# qe.net
KiCad netlist of a schematic drawn in EAGLE
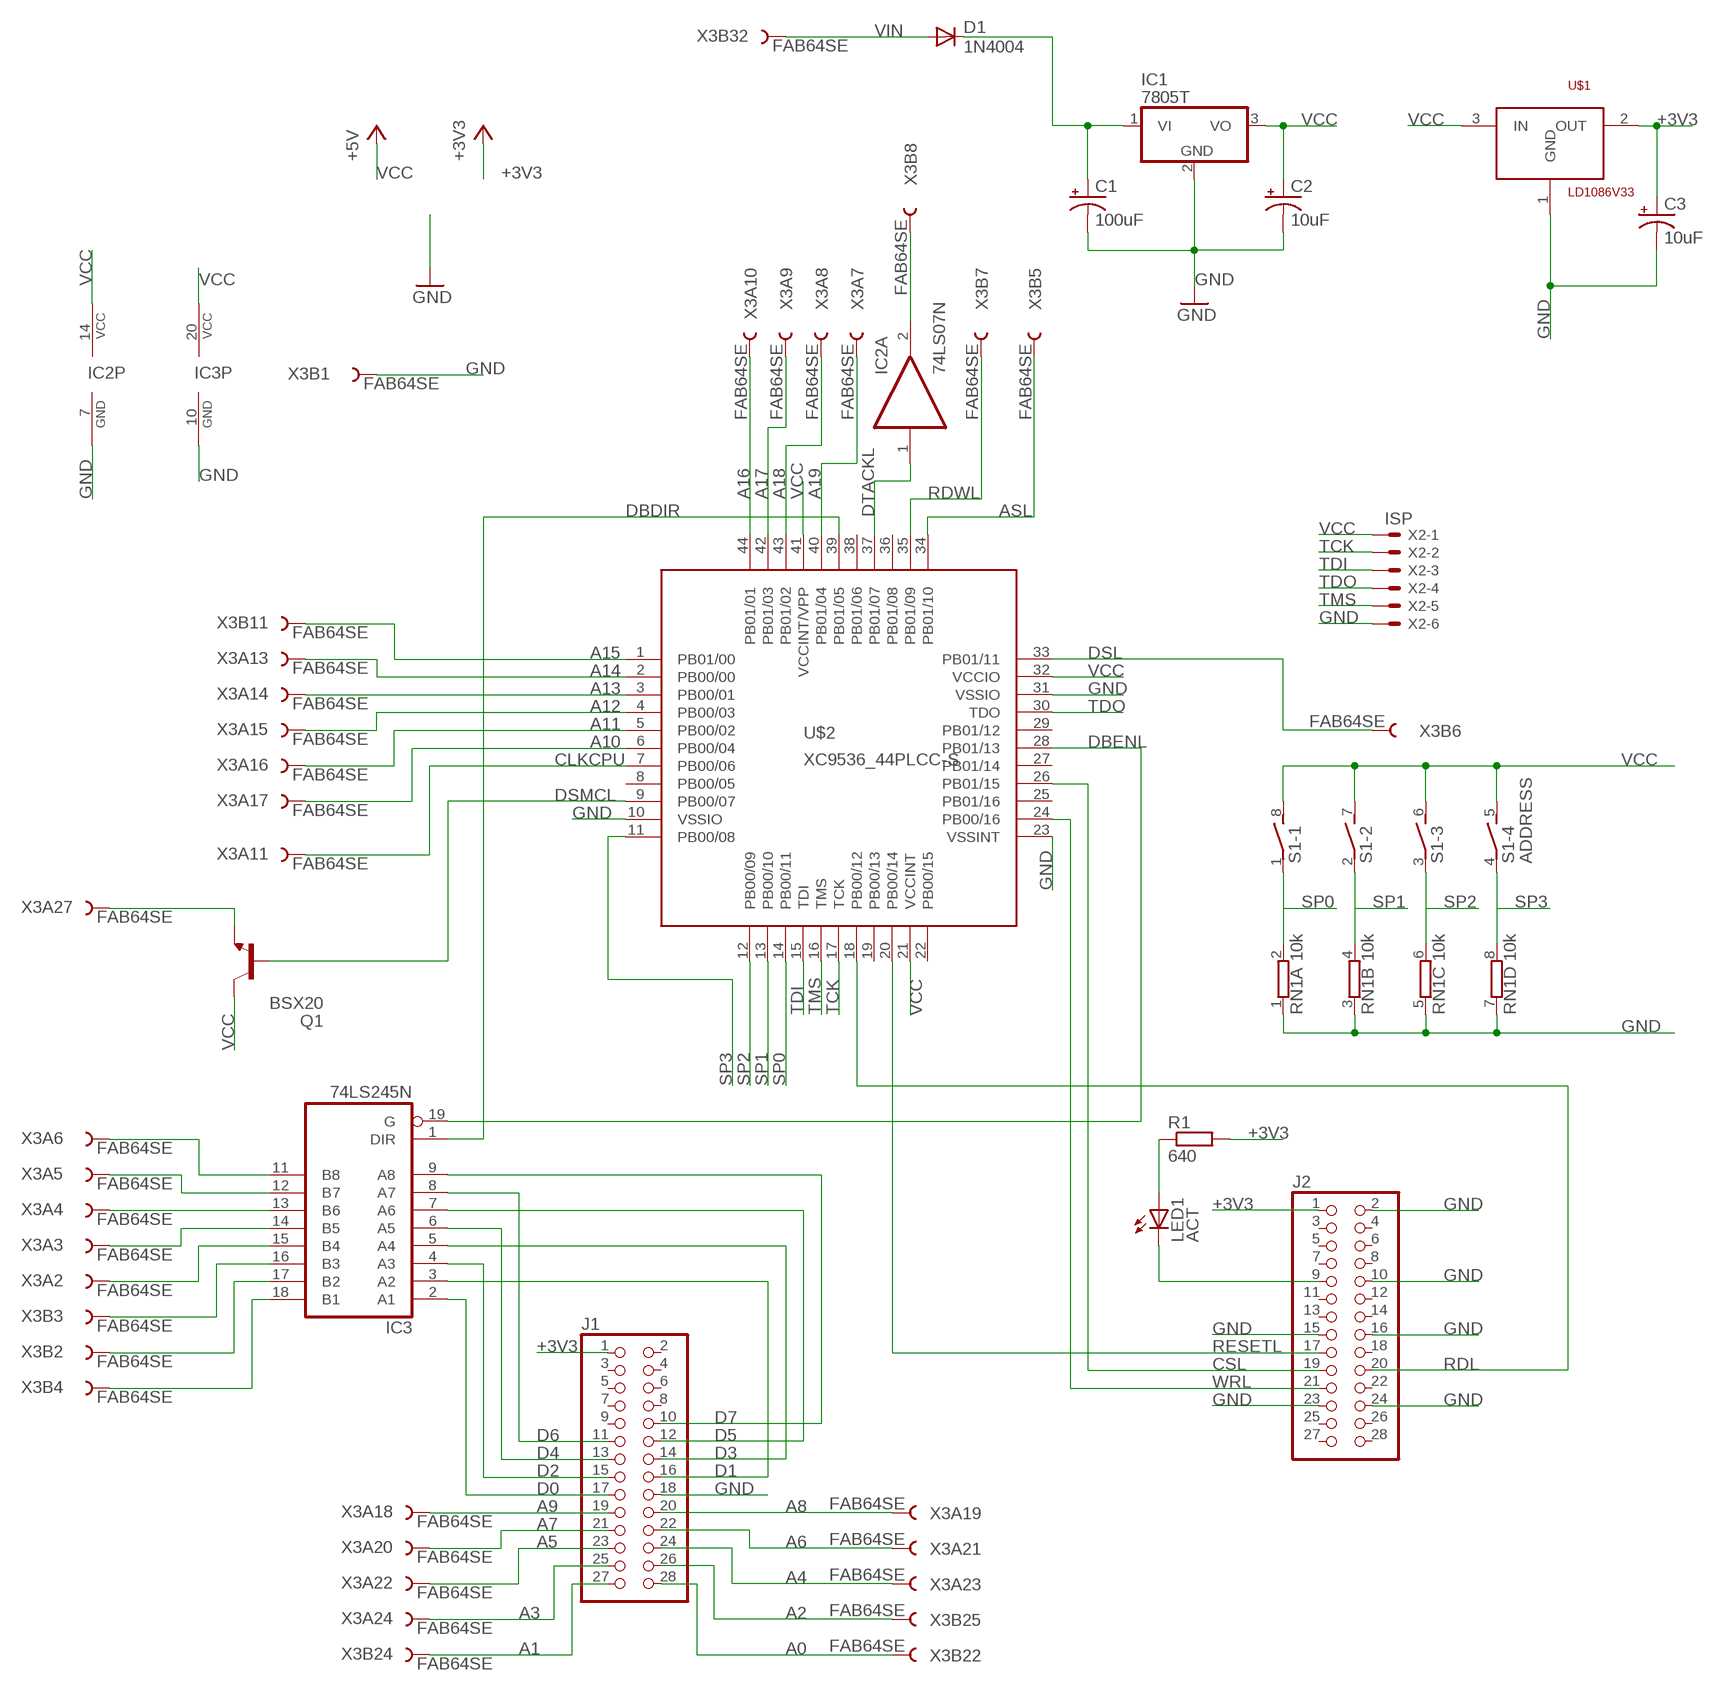
[diagram p0: schematic, sheet 1]

(export (version "E")
  (design (tool "Eeschema 10.0.6"))
  (components
    (comp (ref "C1")
      (value "100uF")
      (footprint "eagle-import:TAP5-80")
      (libsource (lib "eagle-import") (part "CPOL-USTAP5-80"))
    )
    (comp (ref "C2")
      (value "10uF")
      (footprint "eagle-import:TAP5-45")
      (libsource (lib "eagle-import") (part "CPOL-USTAP5-45"))
    )
    (comp (ref "C3")
      (value "10uF")
      (footprint "eagle-import:TAP5-45")
      (libsource (lib "eagle-import") (part "CPOL-USTAP5-45"))
    )
    (comp (ref "D1")
      (value "1N4004")
      (footprint "eagle-import:DO41-10")
      (libsource (lib "eagle-import") (part "1N4004"))
    )
    (comp (ref "IC1")
      (value "7805T")
      (footprint "eagle-import:TO220H")
      (libsource (lib "eagle-import") (part "78T05"))
    )
    (comp (ref "IC2")
      (value "74LS07N")
      (footprint "eagle-import:DIL14")
      (libsource (lib "eagle-import") (part "7407NLS"))
    )
    (comp (ref "IC3")
      (value "74LS245N")
      (footprint "eagle-import:DIL20")
      (libsource (lib "eagle-import") (part "74245NLS"))
    )
    (comp (ref "J1")
      (value "PINHD-2X14")
      (footprint "eagle-import:2X14")
      (libsource (lib "eagle-import") (part "PINHD-2X14"))
    )
    (comp (ref "J2")
      (value "PINHD-2X14")
      (footprint "eagle-import:2X14")
      (libsource (lib "eagle-import") (part "PINHD-2X14"))
    )
    (comp (ref "LED1")
      (value "ACT")
      (footprint "eagle-import:LED5MM")
      (libsource (lib "eagle-import") (part "LED5MM"))
    )
    (comp (ref "Q1")
      (value "BSX20")
      (footprint "eagle-import:TO18")
      (libsource (lib "eagle-import") (part "BSX20"))
    )
    (comp (ref "R1")
      (value "640")
      (footprint "eagle-import:0204_7")
      (libsource (lib "eagle-import") (part "R-EU_0204/7"))
    )
    (comp (ref "RN1")
      (value "10k")
      (footprint "eagle-import:SIL8")
      (libsource (lib "eagle-import") (part "E4R"))
    )
    (comp (ref "S1")
      (value "ADDRESS")
      (footprint "eagle-import:DIP04S")
      (libsource (lib "eagle-import") (part "DIP04S"))
    )
    (comp (ref "U$1")
      (value "LD1086V33")
      (footprint "eagle-import:TO220")
      (libsource (lib "eagle-import") (part "LD1086V33"))
    )
    (comp (ref "U$2")
      (value "XC9536_44PLCC-S")
      (footprint "eagle-import:PLCC44-S")
      (libsource (lib "eagle-import") (part "XC9536_44PLCC-S"))
    )
    (comp (ref "X2")
      (value "ISP")
      (footprint "eagle-import:22-23-2061")
      (libsource (lib "eagle-import") (part "22-23-2061"))
    )
    (comp (ref "X3")
      (value "FAB64SE")
      (footprint "eagle-import:FAB64S")
      (libsource (lib "eagle-import") (part "FAB64SE"))
    )
  )
  (nets
    (net (code "1") (name "+3V3") (class "Default")
      (node (ref "C3") (pin "+") (pinfunction "+_+") (pintype "passive"))
      (node (ref "J1") (pin "1") (pinfunction "1_1") (pintype "passive"))
      (node (ref "J2") (pin "1") (pinfunction "1_1") (pintype "passive"))
      (node (ref "R1") (pin "2") (pinfunction "2_2") (pintype "passive"))
      (node (ref "U$1") (pin "2") (pinfunction "OUT_2") (pintype "bidirectional"))
    )
    (net (code "2") (name "+5V") (class "Default")
      (node (ref "C2") (pin "+") (pinfunction "+_+") (pintype "passive"))
      (node (ref "IC1") (pin "3") (pinfunction "VO_3") (pintype "passive"))
      (node (ref "IC2") (pin "14") (pinfunction "VCC_14") (pintype "power_in"))
      (node (ref "IC3") (pin "20") (pinfunction "VCC_20") (pintype "power_in"))
      (node (ref "Q1") (pin "3") (pinfunction "C_3") (pintype "passive"))
      (node (ref "S1") (pin "5") (pinfunction "2_5") (pintype "passive"))
      (node (ref "S1") (pin "6") (pinfunction "2_6") (pintype "passive"))
      (node (ref "S1") (pin "7") (pinfunction "2_7") (pintype "passive"))
      (node (ref "S1") (pin "8") (pinfunction "2_8") (pintype "passive"))
      (node (ref "U$1") (pin "3") (pinfunction "IN_3") (pintype "bidirectional"))
      (node (ref "U$2") (pin "21") (pinfunction "VCCINT_21") (pintype "power_in"))
      (node (ref "U$2") (pin "32") (pinfunction "VCCIO_32") (pintype "power_in"))
      (node (ref "U$2") (pin "41") (pinfunction "VCCINT/VPP_41") (pintype "input"))
      (node (ref "X2") (pin "1") (pinfunction "S_1") (pintype "passive"))
    )
    (net (code "3") (name "/A0") (class "Default")
      (node (ref "J1") (pin "28") (pinfunction "28_28") (pintype "passive"))
      (node (ref "X3") (pin "B22") (pinfunction "B_B22") (pintype "passive"))
    )
    (net (code "4") (name "/A1") (class "Default")
      (node (ref "J1") (pin "27") (pinfunction "27_27") (pintype "passive"))
      (node (ref "X3") (pin "B24") (pinfunction "B_B24") (pintype "passive"))
    )
    (net (code "5") (name "/A2") (class "Default")
      (node (ref "J1") (pin "26") (pinfunction "26_26") (pintype "passive"))
      (node (ref "X3") (pin "B25") (pinfunction "B_B25") (pintype "passive"))
    )
    (net (code "6") (name "/A3") (class "Default")
      (node (ref "J1") (pin "25") (pinfunction "25_25") (pintype "passive"))
      (node (ref "X3") (pin "A24") (pinfunction "B_A24") (pintype "passive"))
    )
    (net (code "7") (name "/A4") (class "Default")
      (node (ref "J1") (pin "24") (pinfunction "24_24") (pintype "passive"))
      (node (ref "X3") (pin "A23") (pinfunction "B_A23") (pintype "passive"))
    )
    (net (code "8") (name "/A5") (class "Default")
      (node (ref "J1") (pin "23") (pinfunction "23_23") (pintype "passive"))
      (node (ref "X3") (pin "A22") (pinfunction "B_A22") (pintype "passive"))
    )
    (net (code "9") (name "/A6") (class "Default")
      (node (ref "J1") (pin "22") (pinfunction "22_22") (pintype "passive"))
      (node (ref "X3") (pin "A21") (pinfunction "B_A21") (pintype "passive"))
    )
    (net (code "10") (name "/A7") (class "Default")
      (node (ref "J1") (pin "21") (pinfunction "21_21") (pintype "passive"))
      (node (ref "X3") (pin "A20") (pinfunction "B_A20") (pintype "passive"))
    )
    (net (code "11") (name "/A8") (class "Default")
      (node (ref "J1") (pin "20") (pinfunction "20_20") (pintype "passive"))
      (node (ref "X3") (pin "A19") (pinfunction "B_A19") (pintype "passive"))
    )
    (net (code "12") (name "/A9") (class "Default")
      (node (ref "J1") (pin "19") (pinfunction "19_19") (pintype "passive"))
      (node (ref "X3") (pin "A18") (pinfunction "B_A18") (pintype "passive"))
    )
    (net (code "13") (name "/A10") (class "Default")
      (node (ref "U$2") (pin "6") (pinfunction "PB00/04_6") (pintype "bidirectional"))
      (node (ref "X3") (pin "A17") (pinfunction "B_A17") (pintype "passive"))
    )
    (net (code "14") (name "/A11") (class "Default")
      (node (ref "U$2") (pin "5") (pinfunction "PB00/02_5") (pintype "bidirectional"))
      (node (ref "X3") (pin "A16") (pinfunction "B_A16") (pintype "passive"))
    )
    (net (code "15") (name "/A12") (class "Default")
      (node (ref "U$2") (pin "4") (pinfunction "PB00/03_4") (pintype "bidirectional"))
      (node (ref "X3") (pin "A15") (pinfunction "B_A15") (pintype "passive"))
    )
    (net (code "16") (name "/A13") (class "Default")
      (node (ref "U$2") (pin "3") (pinfunction "PB00/01_3") (pintype "bidirectional"))
      (node (ref "X3") (pin "A14") (pinfunction "B_A14") (pintype "passive"))
    )
    (net (code "17") (name "/A14") (class "Default")
      (node (ref "U$2") (pin "2") (pinfunction "PB00/00_2") (pintype "bidirectional"))
      (node (ref "X3") (pin "A13") (pinfunction "B_A13") (pintype "passive"))
    )
    (net (code "18") (name "/A15") (class "Default")
      (node (ref "U$2") (pin "1") (pinfunction "PB01/00_1") (pintype "bidirectional"))
      (node (ref "X3") (pin "B11") (pinfunction "B_B11") (pintype "passive"))
    )
    (net (code "19") (name "/A16") (class "Default")
      (node (ref "U$2") (pin "44") (pinfunction "PB01/01_44") (pintype "bidirectional"))
      (node (ref "X3") (pin "A10") (pinfunction "B_A10") (pintype "passive"))
    )
    (net (code "20") (name "/A17") (class "Default")
      (node (ref "U$2") (pin "42") (pinfunction "PB01/03_42") (pintype "bidirectional"))
      (node (ref "X3") (pin "A9") (pinfunction "B_A9") (pintype "passive"))
    )
    (net (code "21") (name "/A18") (class "Default")
      (node (ref "U$2") (pin "43") (pinfunction "PB01/02_43") (pintype "bidirectional"))
      (node (ref "X3") (pin "A8") (pinfunction "B_A8") (pintype "passive"))
    )
    (net (code "22") (name "/A19") (class "Default")
      (node (ref "U$2") (pin "40") (pinfunction "PB01/04_40") (pintype "bidirectional"))
      (node (ref "X3") (pin "A7") (pinfunction "B_A7") (pintype "passive"))
    )
    (net (code "23") (name "/ASL") (class "Default")
      (node (ref "U$2") (pin "34") (pinfunction "PB01/10_34") (pintype "bidirectional"))
      (node (ref "X3") (pin "B5") (pinfunction "B_B5") (pintype "passive"))
    )
    (net (code "24") (name "/CLKCPU") (class "Default")
      (node (ref "U$2") (pin "7") (pinfunction "PB00/06_7") (pintype "bidirectional"))
      (node (ref "X3") (pin "A11") (pinfunction "B_A11") (pintype "passive"))
    )
    (net (code "25") (name "/CSL") (class "Default")
      (node (ref "J2") (pin "19") (pinfunction "19_19") (pintype "passive"))
      (node (ref "U$2") (pin "26") (pinfunction "PB01/15_26") (pintype "bidirectional"))
    )
    (net (code "26") (name "/D0") (class "Default")
      (node (ref "IC3") (pin "2") (pinfunction "A1_2") (pintype "bidirectional"))
      (node (ref "J1") (pin "17") (pinfunction "17_17") (pintype "passive"))
    )
    (net (code "27") (name "/D1") (class "Default")
      (node (ref "IC3") (pin "3") (pinfunction "A2_3") (pintype "bidirectional"))
      (node (ref "J1") (pin "16") (pinfunction "16_16") (pintype "passive"))
    )
    (net (code "28") (name "/D2") (class "Default")
      (node (ref "IC3") (pin "4") (pinfunction "A3_4") (pintype "bidirectional"))
      (node (ref "J1") (pin "15") (pinfunction "15_15") (pintype "passive"))
    )
    (net (code "29") (name "/D3") (class "Default")
      (node (ref "IC3") (pin "5") (pinfunction "A4_5") (pintype "bidirectional"))
      (node (ref "J1") (pin "14") (pinfunction "14_14") (pintype "passive"))
    )
    (net (code "30") (name "/D4") (class "Default")
      (node (ref "IC3") (pin "6") (pinfunction "A5_6") (pintype "bidirectional"))
      (node (ref "J1") (pin "13") (pinfunction "13_13") (pintype "passive"))
    )
    (net (code "31") (name "/D5") (class "Default")
      (node (ref "IC3") (pin "7") (pinfunction "A6_7") (pintype "bidirectional"))
      (node (ref "J1") (pin "12") (pinfunction "12_12") (pintype "passive"))
    )
    (net (code "32") (name "/D6") (class "Default")
      (node (ref "IC3") (pin "8") (pinfunction "A7_8") (pintype "bidirectional"))
      (node (ref "J1") (pin "11") (pinfunction "11_11") (pintype "passive"))
    )
    (net (code "33") (name "/D7") (class "Default")
      (node (ref "IC3") (pin "9") (pinfunction "A8_9") (pintype "bidirectional"))
      (node (ref "J1") (pin "10") (pinfunction "10_10") (pintype "passive"))
    )
    (net (code "34") (name "/DBDIR") (class "Default")
      (node (ref "IC3") (pin "1") (pinfunction "DIR_1") (pintype "input"))
      (node (ref "U$2") (pin "39") (pinfunction "PB01/05_39") (pintype "bidirectional"))
    )
    (net (code "35") (name "/DBENL") (class "Default")
      (node (ref "IC3") (pin "19") (pinfunction "G_19") (pintype "input"))
      (node (ref "U$2") (pin "28") (pinfunction "PB01/13_28") (pintype "bidirectional"))
    )
    (net (code "36") (name "/DSL") (class "Default")
      (node (ref "U$2") (pin "33") (pinfunction "PB01/11_33") (pintype "bidirectional"))
      (node (ref "X3") (pin "B6") (pinfunction "B_B6") (pintype "passive"))
    )
    (net (code "37") (name "/DSMCL") (class "Default")
      (node (ref "Q1") (pin "2") (pinfunction "B_2") (pintype "passive"))
      (node (ref "U$2") (pin "9") (pinfunction "PB00/07_9") (pintype "bidirectional"))
    )
    (net (code "38") (name "/DTACKL") (class "Default")
      (node (ref "IC2") (pin "1") (pinfunction "I_1") (pintype "input"))
      (node (ref "U$2") (pin "37") (pinfunction "PB01/07_37") (pintype "bidirectional"))
    )
    (net (code "39") (name "/RDL") (class "Default")
      (node (ref "J2") (pin "20") (pinfunction "20_20") (pintype "passive"))
      (node (ref "U$2") (pin "18") (pinfunction "PB00/12_18") (pintype "bidirectional"))
    )
    (net (code "40") (name "/RDWL") (class "Default")
      (node (ref "U$2") (pin "35") (pinfunction "PB01/09_35") (pintype "bidirectional"))
      (node (ref "X3") (pin "B7") (pinfunction "B_B7") (pintype "passive"))
    )
    (net (code "41") (name "/RESETL") (class "Default")
      (node (ref "J2") (pin "17") (pinfunction "17_17") (pintype "passive"))
      (node (ref "U$2") (pin "20") (pinfunction "PB00/14_20") (pintype "bidirectional"))
    )
    (net (code "42") (name "/SP0") (class "Default")
      (node (ref "RN1") (pin "2") (pinfunction "2_2") (pintype "passive"))
      (node (ref "S1") (pin "1") (pinfunction "1_1") (pintype "passive"))
      (node (ref "U$2") (pin "14") (pinfunction "PB00/11_14") (pintype "bidirectional"))
    )
    (net (code "43") (name "/SP1") (class "Default")
      (node (ref "RN1") (pin "4") (pinfunction "2_4") (pintype "passive"))
      (node (ref "S1") (pin "2") (pinfunction "1_2") (pintype "passive"))
      (node (ref "U$2") (pin "13") (pinfunction "PB00/10_13") (pintype "bidirectional"))
    )
    (net (code "44") (name "/SP2") (class "Default")
      (node (ref "RN1") (pin "6") (pinfunction "2_6") (pintype "passive"))
      (node (ref "S1") (pin "3") (pinfunction "1_3") (pintype "passive"))
      (node (ref "U$2") (pin "12") (pinfunction "PB00/09_12") (pintype "bidirectional"))
    )
    (net (code "45") (name "/SP3") (class "Default")
      (node (ref "RN1") (pin "8") (pinfunction "2_8") (pintype "passive"))
      (node (ref "S1") (pin "4") (pinfunction "1_4") (pintype "passive"))
      (node (ref "U$2") (pin "11") (pinfunction "PB00/08_11") (pintype "bidirectional"))
    )
    (net (code "46") (name "/TCK") (class "Default")
      (node (ref "U$2") (pin "17") (pinfunction "TCK_17") (pintype "input"))
      (node (ref "X2") (pin "2") (pinfunction "S_2") (pintype "passive"))
    )
    (net (code "47") (name "/TDI") (class "Default")
      (node (ref "U$2") (pin "15") (pinfunction "TDI_15") (pintype "input"))
      (node (ref "X2") (pin "3") (pinfunction "S_3") (pintype "passive"))
    )
    (net (code "48") (name "/TDO") (class "Default")
      (node (ref "U$2") (pin "30") (pinfunction "TDO_30") (pintype "output"))
      (node (ref "X2") (pin "4") (pinfunction "S_4") (pintype "passive"))
    )
    (net (code "49") (name "/TMS") (class "Default")
      (node (ref "U$2") (pin "16") (pinfunction "TMS_16") (pintype "input"))
      (node (ref "X2") (pin "5") (pinfunction "S_5") (pintype "passive"))
    )
    (net (code "50") (name "/VIN") (class "Default")
      (node (ref "C1") (pin "+") (pinfunction "+_+") (pintype "passive"))
      (node (ref "D1") (pin "C") (pinfunction "C_C") (pintype "passive"))
      (node (ref "IC1") (pin "1") (pinfunction "VI_1") (pintype "input"))
    )
    (net (code "51") (name "/WRL") (class "Default")
      (node (ref "J2") (pin "21") (pinfunction "21_21") (pintype "passive"))
      (node (ref "U$2") (pin "24") (pinfunction "PB00/16_24") (pintype "bidirectional"))
    )
    (net (code "52") (name "GND") (class "Default")
      (node (ref "C1") (pin "-") (pinfunction "-_-") (pintype "passive"))
      (node (ref "C2") (pin "-") (pinfunction "-_-") (pintype "passive"))
      (node (ref "C3") (pin "-") (pinfunction "-_-") (pintype "passive"))
      (node (ref "IC1") (pin "2") (pinfunction "GND_2") (pintype "passive"))
      (node (ref "IC2") (pin "7") (pinfunction "GND_7") (pintype "power_in"))
      (node (ref "IC3") (pin "10") (pinfunction "GND_10") (pintype "power_in"))
      (node (ref "J1") (pin "18") (pinfunction "18_18") (pintype "passive"))
      (node (ref "J2") (pin "10") (pinfunction "10_10") (pintype "passive"))
      (node (ref "J2") (pin "15") (pinfunction "15_15") (pintype "passive"))
      (node (ref "J2") (pin "16") (pinfunction "16_16") (pintype "passive"))
      (node (ref "J2") (pin "2") (pinfunction "2_2") (pintype "passive"))
      (node (ref "J2") (pin "23") (pinfunction "23_23") (pintype "passive"))
      (node (ref "J2") (pin "24") (pinfunction "24_24") (pintype "passive"))
      (node (ref "RN1") (pin "1") (pinfunction "1_1") (pintype "passive"))
      (node (ref "RN1") (pin "3") (pinfunction "1_3") (pintype "passive"))
      (node (ref "RN1") (pin "5") (pinfunction "1_5") (pintype "passive"))
      (node (ref "RN1") (pin "7") (pinfunction "1_7") (pintype "passive"))
      (node (ref "U$1") (pin "1") (pinfunction "GND_1") (pintype "bidirectional"))
      (node (ref "U$2") (pin "10") (pinfunction "VSSIO_10") (pintype "power_in"))
      (node (ref "U$2") (pin "23") (pinfunction "VSSINT_23") (pintype "power_in"))
      (node (ref "U$2") (pin "31") (pinfunction "VSSIO_31") (pintype "power_in"))
      (node (ref "X2") (pin "6") (pinfunction "S_6") (pintype "passive"))
      (node (ref "X3") (pin "B1") (pinfunction "B_B1") (pintype "passive"))
    )
    (net (code "53") (name "Net-(IC2A-O)") (class "Default")
      (node (ref "IC2") (pin "2") (pinfunction "O_2") (pintype "open_collector"))
      (node (ref "X3") (pin "B8") (pinfunction "B_B8") (pintype "passive"))
    )
    (net (code "54") (name "Net-(IC3A-B1)") (class "Default")
      (node (ref "IC3") (pin "18") (pinfunction "B1_18") (pintype "bidirectional"))
      (node (ref "X3") (pin "B4") (pinfunction "B_B4") (pintype "passive"))
    )
    (net (code "55") (name "Net-(IC3A-B2)") (class "Default")
      (node (ref "IC3") (pin "17") (pinfunction "B2_17") (pintype "bidirectional"))
      (node (ref "X3") (pin "B2") (pinfunction "B_B2") (pintype "passive"))
    )
    (net (code "56") (name "Net-(IC3A-B3)") (class "Default")
      (node (ref "IC3") (pin "16") (pinfunction "B3_16") (pintype "bidirectional"))
      (node (ref "X3") (pin "B3") (pinfunction "B_B3") (pintype "passive"))
    )
    (net (code "57") (name "Net-(IC3A-B4)") (class "Default")
      (node (ref "IC3") (pin "15") (pinfunction "B4_15") (pintype "bidirectional"))
      (node (ref "X3") (pin "A2") (pinfunction "B_A2") (pintype "passive"))
    )
    (net (code "58") (name "Net-(IC3A-B5)") (class "Default")
      (node (ref "IC3") (pin "14") (pinfunction "B5_14") (pintype "bidirectional"))
      (node (ref "X3") (pin "A3") (pinfunction "B_A3") (pintype "passive"))
    )
    (net (code "59") (name "Net-(IC3A-B6)") (class "Default")
      (node (ref "IC3") (pin "13") (pinfunction "B6_13") (pintype "bidirectional"))
      (node (ref "X3") (pin "A4") (pinfunction "B_A4") (pintype "passive"))
    )
    (net (code "60") (name "Net-(IC3A-B7)") (class "Default")
      (node (ref "IC3") (pin "12") (pinfunction "B7_12") (pintype "bidirectional"))
      (node (ref "X3") (pin "A5") (pinfunction "B_A5") (pintype "passive"))
    )
    (net (code "61") (name "Net-(IC3A-B8)") (class "Default")
      (node (ref "IC3") (pin "11") (pinfunction "B8_11") (pintype "bidirectional"))
      (node (ref "X3") (pin "A6") (pinfunction "B_A6") (pintype "passive"))
    )
    (net (code "62") (name "Net-(LED1-C)") (class "Default")
      (node (ref "J2") (pin "9") (pinfunction "9_9") (pintype "passive"))
      (node (ref "LED1") (pin "K") (pinfunction "C_K") (pintype "passive"))
    )
    (net (code "63") (name "Net-(LED1-PadA)") (class "Default")
      (node (ref "LED1") (pin "A") (pinfunction "A_A") (pintype "passive"))
      (node (ref "R1") (pin "1") (pinfunction "1_1") (pintype "passive"))
    )
    (net (code "64") (name "Net-(Q1-E)") (class "Default")
      (node (ref "Q1") (pin "1") (pinfunction "E_1") (pintype "passive"))
      (node (ref "X3") (pin "A27") (pinfunction "B_A27") (pintype "passive"))
    )
    (net (code "65") (name "Net-(X3BF-B)") (class "Default")
      (node (ref "D1") (pin "A") (pinfunction "A_A") (pintype "passive"))
      (node (ref "X3") (pin "B32") (pinfunction "B_B32") (pintype "passive"))
    )
    (net (code "66") (name "unconnected-(J1-Pad2)") (class "Default")
      (node (ref "J1") (pin "2") (pinfunction "2_2") (pintype "passive"))
    )
    (net (code "67") (name "unconnected-(J1-Pad3)") (class "Default")
      (node (ref "J1") (pin "3") (pinfunction "3_3") (pintype "passive"))
    )
    (net (code "68") (name "unconnected-(J1-Pad4)") (class "Default")
      (node (ref "J1") (pin "4") (pinfunction "4_4") (pintype "passive"))
    )
    (net (code "69") (name "unconnected-(J1-Pad5)") (class "Default")
      (node (ref "J1") (pin "5") (pinfunction "5_5") (pintype "passive"))
    )
    (net (code "70") (name "unconnected-(J1-Pad6)") (class "Default")
      (node (ref "J1") (pin "6") (pinfunction "6_6") (pintype "passive"))
    )
    (net (code "71") (name "unconnected-(J1-Pad7)") (class "Default")
      (node (ref "J1") (pin "7") (pinfunction "7_7") (pintype "passive"))
    )
    (net (code "72") (name "unconnected-(J1-Pad8)") (class "Default")
      (node (ref "J1") (pin "8") (pinfunction "8_8") (pintype "passive"))
    )
    (net (code "73") (name "unconnected-(J1-Pad9)") (class "Default")
      (node (ref "J1") (pin "9") (pinfunction "9_9") (pintype "passive"))
    )
    (net (code "74") (name "unconnected-(J2-Pad3)") (class "Default")
      (node (ref "J2") (pin "3") (pinfunction "3_3") (pintype "passive"))
    )
    (net (code "75") (name "unconnected-(J2-Pad4)") (class "Default")
      (node (ref "J2") (pin "4") (pinfunction "4_4") (pintype "passive"))
    )
    (net (code "76") (name "unconnected-(J2-Pad5)") (class "Default")
      (node (ref "J2") (pin "5") (pinfunction "5_5") (pintype "passive"))
    )
    (net (code "77") (name "unconnected-(J2-Pad6)") (class "Default")
      (node (ref "J2") (pin "6") (pinfunction "6_6") (pintype "passive"))
    )
    (net (code "78") (name "unconnected-(J2-Pad7)") (class "Default")
      (node (ref "J2") (pin "7") (pinfunction "7_7") (pintype "passive"))
    )
    (net (code "79") (name "unconnected-(J2-Pad8)") (class "Default")
      (node (ref "J2") (pin "8") (pinfunction "8_8") (pintype "passive"))
    )
    (net (code "80") (name "unconnected-(J2-Pad11)") (class "Default")
      (node (ref "J2") (pin "11") (pinfunction "11_11") (pintype "passive"))
    )
    (net (code "81") (name "unconnected-(J2-Pad12)") (class "Default")
      (node (ref "J2") (pin "12") (pinfunction "12_12") (pintype "passive"))
    )
    (net (code "82") (name "unconnected-(J2-Pad13)") (class "Default")
      (node (ref "J2") (pin "13") (pinfunction "13_13") (pintype "passive"))
    )
    (net (code "83") (name "unconnected-(J2-Pad14)") (class "Default")
      (node (ref "J2") (pin "14") (pinfunction "14_14") (pintype "passive"))
    )
    (net (code "84") (name "unconnected-(J2-Pad18)") (class "Default")
      (node (ref "J2") (pin "18") (pinfunction "18_18") (pintype "passive"))
    )
    (net (code "85") (name "unconnected-(J2-Pad22)") (class "Default")
      (node (ref "J2") (pin "22") (pinfunction "22_22") (pintype "passive"))
    )
    (net (code "86") (name "unconnected-(J2-Pad25)") (class "Default")
      (node (ref "J2") (pin "25") (pinfunction "25_25") (pintype "passive"))
    )
    (net (code "87") (name "unconnected-(J2-Pad26)") (class "Default")
      (node (ref "J2") (pin "26") (pinfunction "26_26") (pintype "passive"))
    )
    (net (code "88") (name "unconnected-(J2-Pad27)") (class "Default")
      (node (ref "J2") (pin "27") (pinfunction "27_27") (pintype "passive"))
    )
    (net (code "89") (name "unconnected-(J2-Pad28)") (class "Default")
      (node (ref "J2") (pin "28") (pinfunction "28_28") (pintype "passive"))
    )
    (net (code "90") (name "unconnected-(U$2-PB00{slash}05-Pad8)") (class "Default")
      (node (ref "U$2") (pin "8") (pinfunction "PB00/05_8") (pintype "bidirectional"))
    )
    (net (code "91") (name "unconnected-(U$2-PB00{slash}13-Pad19)") (class "Default")
      (node (ref "U$2") (pin "19") (pinfunction "PB00/13_19") (pintype "bidirectional"))
    )
    (net (code "92") (name "unconnected-(U$2-PB00{slash}15-Pad22)") (class "Default")
      (node (ref "U$2") (pin "22") (pinfunction "PB00/15_22") (pintype "bidirectional"))
    )
    (net (code "93") (name "unconnected-(U$2-PB01{slash}06-Pad38)") (class "Default")
      (node (ref "U$2") (pin "38") (pinfunction "PB01/06_38") (pintype "bidirectional"))
    )
    (net (code "94") (name "unconnected-(U$2-PB01{slash}08-Pad36)") (class "Default")
      (node (ref "U$2") (pin "36") (pinfunction "PB01/08_36") (pintype "bidirectional"))
    )
    (net (code "95") (name "unconnected-(U$2-PB01{slash}12-Pad29)") (class "Default")
      (node (ref "U$2") (pin "29") (pinfunction "PB01/12_29") (pintype "bidirectional"))
    )
    (net (code "96") (name "unconnected-(U$2-PB01{slash}14-Pad27)") (class "Default")
      (node (ref "U$2") (pin "27") (pinfunction "PB01/14_27") (pintype "bidirectional"))
    )
    (net (code "97") (name "unconnected-(U$2-PB01{slash}16-Pad25)") (class "Default")
      (node (ref "U$2") (pin "25") (pinfunction "PB01/16_25") (pintype "bidirectional"))
    )
  )
)
